# Timer_CMD_REV2.net
KiCad netlist of a schematic drawn in EAGLE
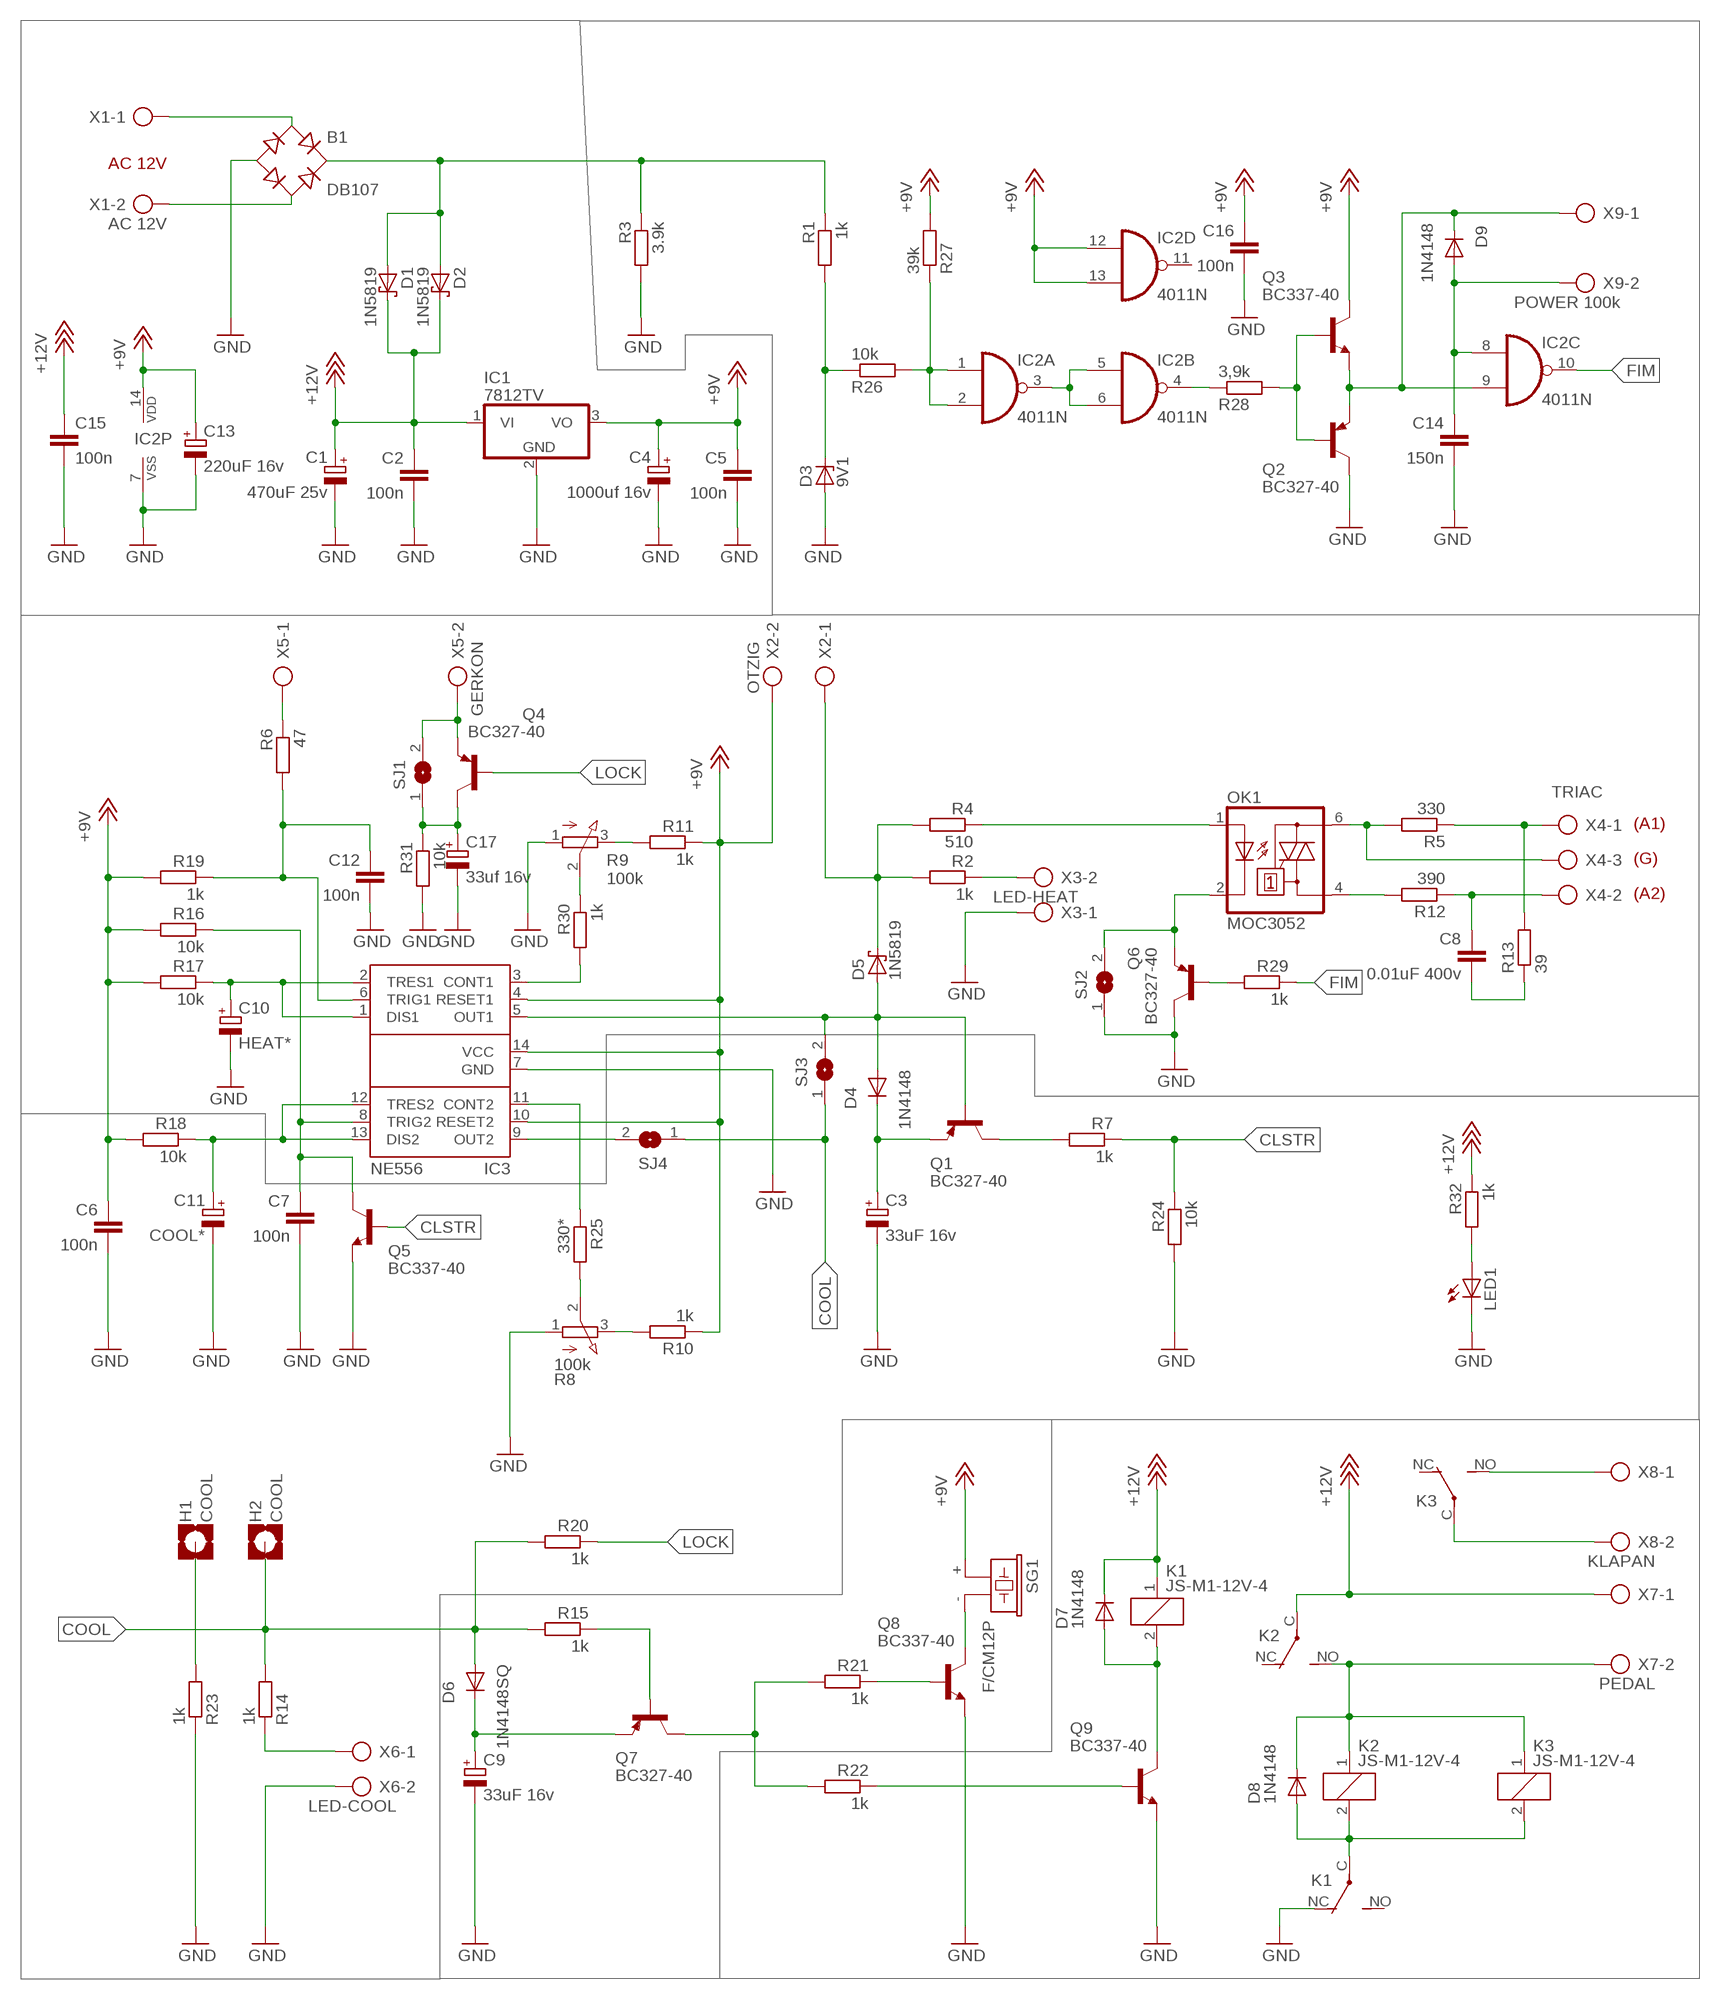
[diagram p0: schematic, sheet 1]

(export (version "E")
  (design (tool "Eeschema 10.0.6"))
  (components
    (comp (ref "B1")
      (value "DB107")
      (footprint "eagle-import:DB")
      (libsource (lib "eagle-import") (part "DB?GDB107"))
    )
    (comp (ref "C1")
      (value "470uF 25v")
      (footprint "eagle-import:E3,5-8")
      (libsource (lib "eagle-import") (part "CPOL-EUE3.5-8"))
    )
    (comp (ref "C2")
      (value "100n")
      (footprint "eagle-import:C050-035X075")
      (libsource (lib "eagle-import") (part "C-EU050-035X075"))
    )
    (comp (ref "C3")
      (value "33uF 16v")
      (footprint "eagle-import:E3,5-8")
      (libsource (lib "eagle-import") (part "CPOL-EUE3.5-8"))
    )
    (comp (ref "C4")
      (value "1000uf 16v")
      (footprint "eagle-import:E5-10,5")
      (libsource (lib "eagle-import") (part "CPOL-EUE5-10.5"))
    )
    (comp (ref "C5")
      (value "100n")
      (footprint "eagle-import:C050-035X075")
      (libsource (lib "eagle-import") (part "C-EU050-035X075"))
    )
    (comp (ref "C6")
      (value "100n")
      (footprint "eagle-import:C025-030X050")
      (libsource (lib "eagle-import") (part "C-EU025-030X050"))
    )
    (comp (ref "C7")
      (value "100n")
      (footprint "eagle-import:C025-030X050")
      (libsource (lib "eagle-import") (part "C-EU025-030X050"))
    )
    (comp (ref "C8")
      (value "0.01uF 400v")
      (footprint "eagle-import:C075-063X106")
      (libsource (lib "eagle-import") (part "C-EU075-063X106"))
    )
    (comp (ref "C9")
      (value "33uF 16v")
      (footprint "eagle-import:E3,5-8")
      (libsource (lib "eagle-import") (part "CPOL-EUE3.5-8"))
    )
    (comp (ref "C10")
      (value "HEAT*")
      (footprint "eagle-import:E3,5-10")
      (libsource (lib "eagle-import") (part "CPOL-EUE3.5-10"))
    )
    (comp (ref "C11")
      (value "COOL*")
      (footprint "eagle-import:E3,5-10")
      (libsource (lib "eagle-import") (part "CPOL-EUE3.5-10"))
    )
    (comp (ref "C12")
      (value "100n")
      (footprint "eagle-import:C025-030X050")
      (libsource (lib "eagle-import") (part "C-EU025-030X050"))
    )
    (comp (ref "C13")
      (value "220uF 16v")
      (footprint "eagle-import:E3,5-8")
      (libsource (lib "eagle-import") (part "CPOL-EUE3.5-8"))
    )
    (comp (ref "C14")
      (value "150n")
      (footprint "eagle-import:C050-035X075")
      (libsource (lib "eagle-import") (part "C-EU050-035X075"))
    )
    (comp (ref "C15")
      (value "100n")
      (footprint "eagle-import:C050-035X075")
      (libsource (lib "eagle-import") (part "C-EU050-035X075"))
    )
    (comp (ref "C16")
      (value "100n")
      (footprint "eagle-import:C050-035X075")
      (libsource (lib "eagle-import") (part "C-EU050-035X075"))
    )
    (comp (ref "C17")
      (value "33uf 16v")
      (footprint "eagle-import:E2,5-6")
      (libsource (lib "eagle-import") (part "CPOL-EUE2.5-6"))
    )
    (comp (ref "D1")
      (value "1N5819")
      (footprint "eagle-import:DO41-7.6")
      (libsource (lib "eagle-import") (part "1N5819-T"))
    )
    (comp (ref "D2")
      (value "1N5819")
      (footprint "eagle-import:DO41-7.6")
      (libsource (lib "eagle-import") (part "1N5819-T"))
    )
    (comp (ref "D3")
      (value "9V1")
      (footprint "eagle-import:DO41Z12")
      (libsource (lib "eagle-import") (part "1N4728_"))
    )
    (comp (ref "D4")
      (value "1N4148")
      (footprint "eagle-import:DO35-7SQ")
      (libsource (lib "eagle-import") (part "1N4148S"))
    )
    (comp (ref "D5")
      (value "1N5819")
      (footprint "eagle-import:DO41-7.6")
      (libsource (lib "eagle-import") (part "1N5819-T"))
    )
    (comp (ref "D6")
      (value "1N4148SQ")
      (footprint "eagle-import:DO35-10_SQ")
      (libsource (lib "eagle-import") (part "1N4148SQ"))
    )
    (comp (ref "D7")
      (value "1N4148")
      (footprint "eagle-import:DO35-7SQ")
      (libsource (lib "eagle-import") (part "1N4148S"))
    )
    (comp (ref "D8")
      (value "1N4148")
      (footprint "eagle-import:DO35-7SQ")
      (libsource (lib "eagle-import") (part "1N4148S"))
    )
    (comp (ref "D9")
      (value "1N4148")
      (footprint "eagle-import:DO35-7SQ")
      (libsource (lib "eagle-import") (part "1N4148S"))
    )
    (comp (ref "H1")
      (value "COOL")
      (footprint "eagle-import:4MM-PAD-SQUARE")
      (libsource (lib "eagle-import") (part "MOUNT-PAD-SQUARE"))
    )
    (comp (ref "H2")
      (value "COOL")
      (footprint "eagle-import:4MM-PAD-SQUARE")
      (libsource (lib "eagle-import") (part "MOUNT-PAD-SQUARE"))
    )
    (comp (ref "IC1")
      (value "7812TV")
      (footprint "eagle-import:TO220V")
      (libsource (lib "eagle-import") (part "78TV12"))
    )
    (comp (ref "IC2")
      (value "4011N")
      (footprint "eagle-import:DIL14")
      (libsource (lib "eagle-import") (part "4011N"))
    )
    (comp (ref "IC3")
      (value "NE556")
      (footprint "eagle-import:DIL14")
      (libsource (lib "eagle-import") (part "NE556"))
    )
    (comp (ref "K1")
      (value "JS-M1-12V-4")
      (footprint "eagle-import:JS-M")
      (fields (field (name "MPN") "JSM1-12V-4"))
      (libsource (lib "eagle-import") (part "JS-M1-12V-4"))
    )
    (comp (ref "K2")
      (value "JS-M1-12V-4")
      (footprint "eagle-import:JS-M")
      (fields (field (name "MPN") "JSM1-12V-4"))
      (libsource (lib "eagle-import") (part "JS-M1-12V-4"))
    )
    (comp (ref "K3")
      (value "JS-M1-12V-4")
      (footprint "eagle-import:JS-M")
      (fields (field (name "MPN") "JSM1-12V-4"))
      (libsource (lib "eagle-import") (part "JS-M1-12V-4"))
    )
    (comp (ref "LED1")
      (value "LED3MM")
      (footprint "eagle-import:LED3MM")
      (libsource (lib "eagle-import") (part "LED3MM"))
    )
    (comp (ref "OK1")
      (value "MOC3052")
      (footprint "eagle-import:DIL06")
      (fields (field (name "MF") "FAIRCHILD SEMICONDUCTOR") (field (name "MPN") "MOC3042-M"))
      (libsource (lib "eagle-import") (part "MOC3042M"))
    )
    (comp (ref "Q1")
      (value "BC327-40")
      (footprint "eagle-import:TO92-EBC")
      (libsource (lib "eagle-import") (part "BC327-40"))
    )
    (comp (ref "Q2")
      (value "BC327-40")
      (footprint "eagle-import:TO92-EBC")
      (libsource (lib "eagle-import") (part "BC327-40"))
    )
    (comp (ref "Q3")
      (value "BC337-40")
      (footprint "eagle-import:TO92-EBC")
      (libsource (lib "eagle-import") (part "BC338-40"))
    )
    (comp (ref "Q4")
      (value "BC327-40")
      (footprint "eagle-import:TO92-EBC")
      (libsource (lib "eagle-import") (part "BC327-40"))
    )
    (comp (ref "Q5")
      (value "BC337-40")
      (footprint "eagle-import:TO92-EBC")
      (libsource (lib "eagle-import") (part "BC338-40"))
    )
    (comp (ref "Q6")
      (value "BC327-40")
      (footprint "eagle-import:TO92-EBC")
      (libsource (lib "eagle-import") (part "BC327-40"))
    )
    (comp (ref "Q7")
      (value "BC327-40")
      (footprint "eagle-import:TO92-EBC")
      (libsource (lib "eagle-import") (part "BC327-40"))
    )
    (comp (ref "Q8")
      (value "BC337-40")
      (footprint "eagle-import:TO92-EBC")
      (libsource (lib "eagle-import") (part "BC338-40"))
    )
    (comp (ref "Q9")
      (value "BC337-40")
      (footprint "eagle-import:TO92-EBC")
      (libsource (lib "eagle-import") (part "BC338-40"))
    )
    (comp (ref "R1")
      (value "1k")
      (footprint "eagle-import:0207_10")
      (libsource (lib "eagle-import") (part "R-EU_0207/10"))
    )
    (comp (ref "R2")
      (value "1k")
      (footprint "eagle-import:0207_10")
      (libsource (lib "eagle-import") (part "R-EU_0207/10"))
    )
    (comp (ref "R3")
      (value "3.9k")
      (footprint "eagle-import:0207_10")
      (libsource (lib "eagle-import") (part "R-EU_0207/10"))
    )
    (comp (ref "R4")
      (value "510")
      (footprint "eagle-import:0207_10")
      (libsource (lib "eagle-import") (part "R-EU_0207/10"))
    )
    (comp (ref "R5")
      (value "330")
      (footprint "eagle-import:0207_10")
      (libsource (lib "eagle-import") (part "R-EU_0207/10"))
    )
    (comp (ref "R6")
      (value "47")
      (footprint "eagle-import:0207_10")
      (libsource (lib "eagle-import") (part "R-EU_0207/10"))
    )
    (comp (ref "R7")
      (value "1k")
      (footprint "eagle-import:0207_10")
      (libsource (lib "eagle-import") (part "R-EU_0207/10"))
    )
    (comp (ref "R8")
      (value "100k")
      (footprint "eagle-import:3RP_1610N")
      (libsource (lib "eagle-import") (part "3RP/1610N"))
    )
    (comp (ref "R9")
      (value "100k")
      (footprint "eagle-import:3RP_1610N")
      (libsource (lib "eagle-import") (part "3RP/1610N"))
    )
    (comp (ref "R10")
      (value "1k")
      (footprint "eagle-import:0207_10")
      (libsource (lib "eagle-import") (part "R-EU_0207/10"))
    )
    (comp (ref "R11")
      (value "1k")
      (footprint "eagle-import:0207_10")
      (libsource (lib "eagle-import") (part "R-EU_0207/10"))
    )
    (comp (ref "R12")
      (value "390")
      (footprint "eagle-import:0207_10")
      (libsource (lib "eagle-import") (part "R-EU_0207/10"))
    )
    (comp (ref "R13")
      (value "39")
      (footprint "eagle-import:0411_12")
      (libsource (lib "eagle-import") (part "R-EU_0411/12"))
    )
    (comp (ref "R14")
      (value "1k")
      (footprint "eagle-import:0207_10")
      (libsource (lib "eagle-import") (part "R-EU_0207/10"))
    )
    (comp (ref "R15")
      (value "1k")
      (footprint "eagle-import:0207_10")
      (libsource (lib "eagle-import") (part "R-EU_0207/10"))
    )
    (comp (ref "R16")
      (value "10k")
      (footprint "eagle-import:0207_10")
      (libsource (lib "eagle-import") (part "R-EU_0207/10"))
    )
    (comp (ref "R17")
      (value "10k")
      (footprint "eagle-import:0207_10")
      (libsource (lib "eagle-import") (part "R-EU_0207/10"))
    )
    (comp (ref "R18")
      (value "10k")
      (footprint "eagle-import:0207_10")
      (libsource (lib "eagle-import") (part "R-EU_0207/10"))
    )
    (comp (ref "R19")
      (value "1k")
      (footprint "eagle-import:0207_10")
      (libsource (lib "eagle-import") (part "R-EU_0207/10"))
    )
    (comp (ref "R20")
      (value "1k")
      (footprint "eagle-import:0207_10")
      (libsource (lib "eagle-import") (part "R-EU_0207/10"))
    )
    (comp (ref "R21")
      (value "1k")
      (footprint "eagle-import:0207_10")
      (libsource (lib "eagle-import") (part "R-EU_0207/10"))
    )
    (comp (ref "R22")
      (value "1k")
      (footprint "eagle-import:0207_10")
      (libsource (lib "eagle-import") (part "R-EU_0207/10"))
    )
    (comp (ref "R23")
      (value "1k")
      (footprint "eagle-import:0207_10")
      (libsource (lib "eagle-import") (part "R-EU_0207/10"))
    )
    (comp (ref "R24")
      (value "10k")
      (footprint "eagle-import:0207_10")
      (libsource (lib "eagle-import") (part "R-EU_0207/10"))
    )
    (comp (ref "R25")
      (value "330*")
      (footprint "eagle-import:0207_10")
      (libsource (lib "eagle-import") (part "R-EU_0207/10"))
    )
    (comp (ref "R26")
      (value "10k")
      (footprint "eagle-import:0207_10")
      (libsource (lib "eagle-import") (part "R-EU_0207/10"))
    )
    (comp (ref "R27")
      (value "39k")
      (footprint "eagle-import:0207_10")
      (libsource (lib "eagle-import") (part "R-EU_0207/10"))
    )
    (comp (ref "R28")
      (value "3,9k")
      (footprint "eagle-import:0207_10")
      (libsource (lib "eagle-import") (part "R-EU_0207/10"))
    )
    (comp (ref "R29")
      (value "1k")
      (footprint "eagle-import:0207_10")
      (libsource (lib "eagle-import") (part "R-EU_0207/10"))
    )
    (comp (ref "R30")
      (value "1k")
      (footprint "eagle-import:0207_11")
      (libsource (lib "eagle-import") (part "R-EU_0207/11"))
    )
    (comp (ref "R31")
      (value "10k")
      (footprint "eagle-import:0207_10")
      (libsource (lib "eagle-import") (part "R-EU_0207/10"))
    )
    (comp (ref "R32")
      (value "1k")
      (footprint "eagle-import:0207_10")
      (libsource (lib "eagle-import") (part "R-EU_0207/10"))
    )
    (comp (ref "SG1")
      (value "F/CM12P")
      (footprint "eagle-import:F_CM12P")
      (libsource (lib "eagle-import") (part "F/CM12P"))
    )
    (comp (ref "SJ1") (value "SJ") (footprint "eagle-import:SJ") (libsource (lib "eagle-import") (part "SJ")))
    (comp (ref "SJ2") (value "SJ") (footprint "eagle-import:SJ") (libsource (lib "eagle-import") (part "SJ")))
    (comp (ref "SJ3") (value "SJ") (footprint "eagle-import:SJ") (libsource (lib "eagle-import") (part "SJ")))
    (comp (ref "SJ4") (value "SJ") (footprint "eagle-import:SJ") (libsource (lib "eagle-import") (part "SJ")))
    (comp (ref "X1")
      (value "AC 12V")
      (footprint "eagle-import:AK500_2")
      (libsource (lib "eagle-import") (part "AK500/2"))
    )
    (comp (ref "X2")
      (value "OTZIG")
      (footprint "eagle-import:AK500_2")
      (libsource (lib "eagle-import") (part "AK500/2"))
    )
    (comp (ref "X3")
      (value "LED-HEAT")
      (footprint "eagle-import:AK500_2")
      (libsource (lib "eagle-import") (part "AK500/2"))
    )
    (comp (ref "X4")
      (value "TRIAC")
      (footprint "eagle-import:AK500_3")
      (libsource (lib "eagle-import") (part "AK500/3"))
    )
    (comp (ref "X5")
      (value "GERKON")
      (footprint "eagle-import:AK500_2")
      (libsource (lib "eagle-import") (part "AK500/2"))
    )
    (comp (ref "X6")
      (value "LED-COOL")
      (footprint "eagle-import:AK500_2")
      (libsource (lib "eagle-import") (part "AK500/2"))
    )
    (comp (ref "X7")
      (value "PEDAL")
      (footprint "eagle-import:AK500_2")
      (libsource (lib "eagle-import") (part "AK500/2"))
    )
    (comp (ref "X8")
      (value "KLAPAN")
      (footprint "eagle-import:AK500_2")
      (libsource (lib "eagle-import") (part "AK500/2"))
    )
    (comp (ref "X9")
      (value "POWER 100k")
      (footprint "eagle-import:AK500_2")
      (libsource (lib "eagle-import") (part "AK500/2"))
    )
  )
  (nets
    (net (code "1") (name "+9V") (class "Default")
      (node (ref "C13") (pin "+") (pinfunction "+_+") (pintype "passive"))
      (node (ref "C16") (pin "1") (pinfunction "1_1") (pintype "passive"))
      (node (ref "C4") (pin "+") (pinfunction "+_+") (pintype "passive"))
      (node (ref "C5") (pin "1") (pinfunction "1_1") (pintype "passive"))
      (node (ref "C6") (pin "1") (pinfunction "1_1") (pintype "passive"))
      (node (ref "IC1") (pin "3") (pinfunction "VO_3") (pintype "passive"))
      (node (ref "IC2") (pin "12") (pinfunction "I0_12") (pintype "input"))
      (node (ref "IC2") (pin "13") (pinfunction "I1_13") (pintype "input"))
      (node (ref "IC2") (pin "14") (pinfunction "VDD_14") (pintype "power_in"))
      (node (ref "IC3") (pin "10") (pinfunction "RESET2_10") (pintype "input"))
      (node (ref "IC3") (pin "14") (pinfunction "VCC_14") (pintype "power_in"))
      (node (ref "IC3") (pin "4") (pinfunction "RESET1_4") (pintype "input"))
      (node (ref "Q3") (pin "C") (pinfunction "C_C") (pintype "passive"))
      (node (ref "R10") (pin "1") (pinfunction "1_1") (pintype "passive"))
      (node (ref "R11") (pin "1") (pinfunction "1_1") (pintype "passive"))
      (node (ref "R16") (pin "2") (pinfunction "2_2") (pintype "passive"))
      (node (ref "R17") (pin "2") (pinfunction "2_2") (pintype "passive"))
      (node (ref "R18") (pin "2") (pinfunction "2_2") (pintype "passive"))
      (node (ref "R19") (pin "2") (pinfunction "2_2") (pintype "passive"))
      (node (ref "R27") (pin "2") (pinfunction "2_2") (pintype "passive"))
      (node (ref "SG1") (pin "+") (pinfunction "1_+") (pintype "passive"))
      (node (ref "X2") (pin "2") (pinfunction "KL_2") (pintype "passive"))
    )
    (net (code "2") (name "+12V") (class "Default")
      (node (ref "C1") (pin "+") (pinfunction "+_+") (pintype "passive"))
      (node (ref "C15") (pin "1") (pinfunction "1_1") (pintype "passive"))
      (node (ref "C2") (pin "1") (pinfunction "1_1") (pintype "passive"))
      (node (ref "D1") (pin "C") (pinfunction "C_C") (pintype "passive"))
      (node (ref "D2") (pin "C") (pinfunction "C_C") (pintype "passive"))
      (node (ref "D7") (pin "C") (pinfunction "C_C") (pintype "passive"))
      (node (ref "IC1") (pin "1") (pinfunction "VI_1") (pintype "input"))
      (node (ref "K1") (pin "1") (pinfunction "1_1") (pintype "passive"))
      (node (ref "K2") (pin "C") (pinfunction "P_C") (pintype "passive"))
      (node (ref "R32") (pin "1") (pinfunction "1_1") (pintype "passive"))
      (node (ref "X7") (pin "1") (pinfunction "KL_1") (pintype "passive"))
    )
    (net (code "3") (name "CLSTR") (class "Default")
      (node (ref "Q5") (pin "B") (pinfunction "B_B") (pintype "passive"))
      (node (ref "R24") (pin "1") (pinfunction "1_1") (pintype "passive"))
      (node (ref "R7") (pin "1") (pinfunction "1_1") (pintype "passive"))
    )
    (net (code "4") (name "COOL") (class "Default")
      (node (ref "D6") (pin "A") (pinfunction "A_A") (pintype "passive"))
      (node (ref "H2") (pin "B2,8") (pinfunction "MOUNT_B2,8") (pintype "passive"))
      (node (ref "R14") (pin "2") (pinfunction "2_2") (pintype "passive"))
      (node (ref "R15") (pin "2") (pinfunction "2_2") (pintype "passive"))
      (node (ref "R20") (pin "2") (pinfunction "2_2") (pintype "passive"))
      (node (ref "SJ3") (pin "1") (pinfunction "1_1") (pintype "passive"))
      (node (ref "SJ4") (pin "1") (pinfunction "1_1") (pintype "passive"))
    )
    (net (code "5") (name "FIM") (class "Default")
      (node (ref "IC2") (pin "10") (pinfunction "O_10") (pintype "output"))
      (node (ref "R29") (pin "1") (pinfunction "1_1") (pintype "passive"))
    )
    (net (code "6") (name "GND") (class "Default")
      (node (ref "B1") (pin "-") (pinfunction "-_-") (pintype "passive"))
      (node (ref "C1") (pin "-") (pinfunction "-_-") (pintype "passive"))
      (node (ref "C10") (pin "-") (pinfunction "-_-") (pintype "passive"))
      (node (ref "C11") (pin "-") (pinfunction "-_-") (pintype "passive"))
      (node (ref "C12") (pin "2") (pinfunction "2_2") (pintype "passive"))
      (node (ref "C13") (pin "-") (pinfunction "-_-") (pintype "passive"))
      (node (ref "C14") (pin "2") (pinfunction "2_2") (pintype "passive"))
      (node (ref "C15") (pin "2") (pinfunction "2_2") (pintype "passive"))
      (node (ref "C16") (pin "2") (pinfunction "2_2") (pintype "passive"))
      (node (ref "C17") (pin "-") (pinfunction "-_-") (pintype "passive"))
      (node (ref "C2") (pin "2") (pinfunction "2_2") (pintype "passive"))
      (node (ref "C3") (pin "-") (pinfunction "-_-") (pintype "passive"))
      (node (ref "C4") (pin "-") (pinfunction "-_-") (pintype "passive"))
      (node (ref "C5") (pin "2") (pinfunction "2_2") (pintype "passive"))
      (node (ref "C6") (pin "2") (pinfunction "2_2") (pintype "passive"))
      (node (ref "C7") (pin "2") (pinfunction "2_2") (pintype "passive"))
      (node (ref "C9") (pin "-") (pinfunction "-_-") (pintype "passive"))
      (node (ref "D3") (pin "A") (pinfunction "A_A") (pintype "passive"))
      (node (ref "IC1") (pin "2") (pinfunction "GND_2") (pintype "passive"))
      (node (ref "IC2") (pin "7") (pinfunction "VSS_7") (pintype "power_in"))
      (node (ref "IC3") (pin "7") (pinfunction "GND_7") (pintype "power_in"))
      (node (ref "K1") (pin "NC") (pinfunction "O_NC") (pintype "passive"))
      (node (ref "LED1") (pin "K") (pinfunction "C_K") (pintype "passive"))
      (node (ref "Q2") (pin "C") (pinfunction "C_C") (pintype "passive"))
      (node (ref "Q5") (pin "E") (pinfunction "E_E") (pintype "passive"))
      (node (ref "Q6") (pin "C") (pinfunction "C_C") (pintype "passive"))
      (node (ref "Q8") (pin "E") (pinfunction "E_E") (pintype "passive"))
      (node (ref "Q9") (pin "E") (pinfunction "E_E") (pintype "passive"))
      (node (ref "R23") (pin "1") (pinfunction "1_1") (pintype "passive"))
      (node (ref "R24") (pin "2") (pinfunction "2_2") (pintype "passive"))
      (node (ref "R3") (pin "2") (pinfunction "2_2") (pintype "passive"))
      (node (ref "R31") (pin "2") (pinfunction "2_2") (pintype "passive"))
      (node (ref "R8") (pin "1") (pinfunction "A_1") (pintype "passive"))
      (node (ref "R9") (pin "1") (pinfunction "A_1") (pintype "passive"))
      (node (ref "SJ2") (pin "1") (pinfunction "1_1") (pintype "passive"))
      (node (ref "X3") (pin "1") (pinfunction "KL_1") (pintype "passive"))
      (node (ref "X6") (pin "2") (pinfunction "KL_2") (pintype "passive"))
    )
    (net (code "7") (name "LOCK") (class "Default")
      (node (ref "Q4") (pin "B") (pinfunction "B_B") (pintype "passive"))
      (node (ref "R20") (pin "1") (pinfunction "1_1") (pintype "passive"))
    )
    (net (code "8") (name "Net-(B1-Pad+)") (class "Default")
      (node (ref "B1") (pin "+") (pinfunction "+_+") (pintype "passive"))
      (node (ref "D1") (pin "A") (pinfunction "A_A") (pintype "passive"))
      (node (ref "D2") (pin "A") (pinfunction "A_A") (pintype "passive"))
      (node (ref "R1") (pin "1") (pinfunction "1_1") (pintype "passive"))
      (node (ref "R3") (pin "1") (pinfunction "1_1") (pintype "passive"))
    )
    (net (code "9") (name "Net-(C3-Pad+)") (class "Default")
      (node (ref "C3") (pin "+") (pinfunction "+_+") (pintype "passive"))
      (node (ref "D4") (pin "C") (pinfunction "C_C") (pintype "passive"))
      (node (ref "Q1") (pin "E") (pinfunction "E_E") (pintype "passive"))
    )
    (net (code "10") (name "Net-(C8-Pad2)") (class "Default")
      (node (ref "C8") (pin "2") (pinfunction "2_2") (pintype "passive"))
      (node (ref "R13") (pin "1") (pinfunction "1_1") (pintype "passive"))
    )
    (net (code "11") (name "Net-(C9-Pad+)") (class "Default")
      (node (ref "C9") (pin "+") (pinfunction "+_+") (pintype "passive"))
      (node (ref "D6") (pin "C") (pinfunction "C_C") (pintype "passive"))
      (node (ref "Q7") (pin "E") (pinfunction "E_E") (pintype "passive"))
    )
    (net (code "12") (name "Net-(C17-Pad+)") (class "Default")
      (node (ref "C17") (pin "+") (pinfunction "+_+") (pintype "passive"))
      (node (ref "Q4") (pin "C") (pinfunction "C_C") (pintype "passive"))
      (node (ref "R31") (pin "1") (pinfunction "1_1") (pintype "passive"))
      (node (ref "SJ1") (pin "1") (pinfunction "1_1") (pintype "passive"))
    )
    (net (code "13") (name "Net-(D3-PadC)") (class "Default")
      (node (ref "D3") (pin "C") (pinfunction "C_C") (pintype "passive"))
      (node (ref "R1") (pin "2") (pinfunction "2_2") (pintype "passive"))
      (node (ref "R26") (pin "1") (pinfunction "1_1") (pintype "passive"))
    )
    (net (code "14") (name "Net-(D7-PadA)") (class "Default")
      (node (ref "D7") (pin "A") (pinfunction "A_A") (pintype "passive"))
      (node (ref "K1") (pin "2") (pinfunction "2_2") (pintype "passive"))
      (node (ref "Q9") (pin "C") (pinfunction "C_C") (pintype "passive"))
    )
    (net (code "15") (name "Net-(H1-MOUNT)") (class "Default")
      (node (ref "H1") (pin "B2,8") (pinfunction "MOUNT_B2,8") (pintype "passive"))
      (node (ref "R23") (pin "2") (pinfunction "2_2") (pintype "passive"))
    )
    (net (code "16") (name "Net-(IC2A-I0)") (class "Default")
      (node (ref "IC2") (pin "1") (pinfunction "I0_1") (pintype "input"))
      (node (ref "IC2") (pin "2") (pinfunction "I1_2") (pintype "input"))
      (node (ref "R26") (pin "2") (pinfunction "2_2") (pintype "passive"))
      (node (ref "R27") (pin "1") (pinfunction "1_1") (pintype "passive"))
    )
    (net (code "17") (name "Net-(IC2A-O)") (class "Default")
      (node (ref "IC2") (pin "3") (pinfunction "O_3") (pintype "output"))
      (node (ref "IC2") (pin "5") (pinfunction "I0_5") (pintype "input"))
      (node (ref "IC2") (pin "6") (pinfunction "I1_6") (pintype "input"))
    )
    (net (code "18") (name "Net-(IC2B-O)") (class "Default")
      (node (ref "IC2") (pin "4") (pinfunction "O_4") (pintype "output"))
      (node (ref "R28") (pin "1") (pinfunction "1_1") (pintype "passive"))
    )
    (net (code "19") (name "Net-(IC2C-I0)") (class "Default")
      (node (ref "C14") (pin "1") (pinfunction "1_1") (pintype "passive"))
      (node (ref "D9") (pin "A") (pinfunction "A_A") (pintype "passive"))
      (node (ref "IC2") (pin "8") (pinfunction "I0_8") (pintype "input"))
      (node (ref "X9") (pin "2") (pinfunction "KL_2") (pintype "passive"))
    )
    (net (code "20") (name "Net-(IC2C-I1)") (class "Default")
      (node (ref "D9") (pin "C") (pinfunction "C_C") (pintype "passive"))
      (node (ref "IC2") (pin "9") (pinfunction "I1_9") (pintype "input"))
      (node (ref "Q2") (pin "E") (pinfunction "E_E") (pintype "passive"))
      (node (ref "Q3") (pin "E") (pinfunction "E_E") (pintype "passive"))
      (node (ref "X9") (pin "1") (pinfunction "KL_1") (pintype "passive"))
    )
    (net (code "21") (name "Net-(IC3-CONT1)") (class "Default")
      (node (ref "IC3") (pin "3") (pinfunction "CONT1_3") (pintype "input"))
      (node (ref "R30") (pin "2") (pinfunction "2_2") (pintype "passive"))
    )
    (net (code "22") (name "Net-(IC3-CONT2)") (class "Default")
      (node (ref "IC3") (pin "11") (pinfunction "CONT2_11") (pintype "input"))
      (node (ref "R25") (pin "1") (pinfunction "1_1") (pintype "passive"))
    )
    (net (code "23") (name "Net-(IC3-DIS1)") (class "Default")
      (node (ref "C10") (pin "+") (pinfunction "+_+") (pintype "passive"))
      (node (ref "IC3") (pin "1") (pinfunction "DIS1_1") (pintype "input"))
      (node (ref "IC3") (pin "2") (pinfunction "TRES1_2") (pintype "input"))
      (node (ref "R17") (pin "1") (pinfunction "1_1") (pintype "passive"))
    )
    (net (code "24") (name "Net-(IC3-DIS2)") (class "Default")
      (node (ref "C11") (pin "+") (pinfunction "+_+") (pintype "passive"))
      (node (ref "IC3") (pin "12") (pinfunction "TRES2_12") (pintype "input"))
      (node (ref "IC3") (pin "13") (pinfunction "DIS2_13") (pintype "input"))
      (node (ref "R18") (pin "1") (pinfunction "1_1") (pintype "passive"))
    )
    (net (code "25") (name "Net-(IC3-OUT1)") (class "Default")
      (node (ref "D4") (pin "A") (pinfunction "A_A") (pintype "passive"))
      (node (ref "D5") (pin "A") (pinfunction "A_A") (pintype "passive"))
      (node (ref "IC3") (pin "5") (pinfunction "OUT1_5") (pintype "output"))
      (node (ref "Q1") (pin "B") (pinfunction "B_B") (pintype "passive"))
      (node (ref "SJ3") (pin "2") (pinfunction "2_2") (pintype "passive"))
    )
    (net (code "26") (name "Net-(IC3-OUT2)") (class "Default")
      (node (ref "IC3") (pin "9") (pinfunction "OUT2_9") (pintype "output"))
      (node (ref "SJ4") (pin "2") (pinfunction "2_2") (pintype "passive"))
    )
    (net (code "27") (name "Net-(IC3-TRIG1)") (class "Default")
      (node (ref "C12") (pin "1") (pinfunction "1_1") (pintype "passive"))
      (node (ref "IC3") (pin "6") (pinfunction "TRIG1_6") (pintype "input"))
      (node (ref "R19") (pin "1") (pinfunction "1_1") (pintype "passive"))
      (node (ref "R6") (pin "2") (pinfunction "2_2") (pintype "passive"))
    )
    (net (code "28") (name "Net-(IC3-TRIG2)") (class "Default")
      (node (ref "C7") (pin "1") (pinfunction "1_1") (pintype "passive"))
      (node (ref "IC3") (pin "8") (pinfunction "TRIG2_8") (pintype "input"))
      (node (ref "Q5") (pin "C") (pinfunction "C_C") (pintype "passive"))
      (node (ref "R16") (pin "1") (pinfunction "1_1") (pintype "passive"))
    )
    (net (code "29") (name "Net-(K1B-P)") (class "Default")
      (node (ref "D8") (pin "A") (pinfunction "A_A") (pintype "passive"))
      (node (ref "K1") (pin "C") (pinfunction "P_C") (pintype "passive"))
      (node (ref "K2") (pin "2") (pinfunction "2_2") (pintype "passive"))
      (node (ref "K3") (pin "2") (pinfunction "2_2") (pintype "passive"))
    )
    (net (code "30") (name "Net-(K2B-S)") (class "Default")
      (node (ref "D8") (pin "C") (pinfunction "C_C") (pintype "passive"))
      (node (ref "K2") (pin "1") (pinfunction "1_1") (pintype "passive"))
      (node (ref "K2") (pin "NO") (pinfunction "S_NO") (pintype "passive"))
      (node (ref "K3") (pin "1") (pinfunction "1_1") (pintype "passive"))
      (node (ref "X7") (pin "2") (pinfunction "KL_2") (pintype "passive"))
    )
    (net (code "31") (name "Net-(K3B-P)") (class "Default")
      (node (ref "K3") (pin "C") (pinfunction "P_C") (pintype "passive"))
      (node (ref "X8") (pin "2") (pinfunction "KL_2") (pintype "passive"))
    )
    (net (code "32") (name "Net-(K3B-S)") (class "Default")
      (node (ref "K3") (pin "NO") (pinfunction "S_NO") (pintype "passive"))
      (node (ref "X8") (pin "1") (pinfunction "KL_1") (pintype "passive"))
    )
    (net (code "33") (name "Net-(LED1-PadA)") (class "Default")
      (node (ref "LED1") (pin "A") (pinfunction "A_A") (pintype "passive"))
      (node (ref "R32") (pin "2") (pinfunction "2_2") (pintype "passive"))
    )
    (net (code "34") (name "Net-(OK1-A)") (class "Default")
      (node (ref "OK1") (pin "1") (pinfunction "A_1") (pintype "passive"))
      (node (ref "R4") (pin "1") (pinfunction "1_1") (pintype "passive"))
    )
    (net (code "35") (name "Net-(OK1-A1)") (class "Default")
      (node (ref "OK1") (pin "4") (pinfunction "A1_4") (pintype "passive"))
      (node (ref "R12") (pin "2") (pinfunction "2_2") (pintype "passive"))
    )
    (net (code "36") (name "Net-(OK1-A2)") (class "Default")
      (node (ref "OK1") (pin "6") (pinfunction "A2_6") (pintype "passive"))
      (node (ref "R5") (pin "2") (pinfunction "2_2") (pintype "passive"))
      (node (ref "X4") (pin "3") (pinfunction "KL_3") (pintype "passive"))
    )
    (net (code "37") (name "Net-(OK1-C)") (class "Default")
      (node (ref "OK1") (pin "2") (pinfunction "C_2") (pintype "passive"))
      (node (ref "Q6") (pin "E") (pinfunction "E_E") (pintype "passive"))
      (node (ref "SJ2") (pin "2") (pinfunction "2_2") (pintype "passive"))
    )
    (net (code "38") (name "Net-(Q1-PadC)") (class "Default")
      (node (ref "Q1") (pin "C") (pinfunction "C_C") (pintype "passive"))
      (node (ref "R7") (pin "2") (pinfunction "2_2") (pintype "passive"))
    )
    (net (code "39") (name "Net-(Q2-PadB)") (class "Default")
      (node (ref "Q2") (pin "B") (pinfunction "B_B") (pintype "passive"))
      (node (ref "Q3") (pin "B") (pinfunction "B_B") (pintype "passive"))
      (node (ref "R28") (pin "2") (pinfunction "2_2") (pintype "passive"))
    )
    (net (code "40") (name "Net-(Q6-PadB)") (class "Default")
      (node (ref "Q6") (pin "B") (pinfunction "B_B") (pintype "passive"))
      (node (ref "R29") (pin "2") (pinfunction "2_2") (pintype "passive"))
    )
    (net (code "41") (name "Net-(Q7-PadB)") (class "Default")
      (node (ref "Q7") (pin "B") (pinfunction "B_B") (pintype "passive"))
      (node (ref "R15") (pin "1") (pinfunction "1_1") (pintype "passive"))
    )
    (net (code "42") (name "Net-(Q7-PadC)") (class "Default")
      (node (ref "Q7") (pin "C") (pinfunction "C_C") (pintype "passive"))
      (node (ref "R21") (pin "2") (pinfunction "2_2") (pintype "passive"))
      (node (ref "R22") (pin "2") (pinfunction "2_2") (pintype "passive"))
    )
    (net (code "43") (name "Net-(Q8-PadB)") (class "Default")
      (node (ref "Q8") (pin "B") (pinfunction "B_B") (pintype "passive"))
      (node (ref "R21") (pin "1") (pinfunction "1_1") (pintype "passive"))
    )
    (net (code "44") (name "Net-(Q9-PadB)") (class "Default")
      (node (ref "Q9") (pin "B") (pinfunction "B_B") (pintype "passive"))
      (node (ref "R22") (pin "1") (pinfunction "1_1") (pintype "passive"))
    )
    (net (code "45") (name "Net-(R8-E)") (class "Default")
      (node (ref "R10") (pin "2") (pinfunction "2_2") (pintype "passive"))
      (node (ref "R8") (pin "3") (pinfunction "E_3") (pintype "passive"))
    )
    (net (code "46") (name "Net-(R8-S)") (class "Default")
      (node (ref "R25") (pin "2") (pinfunction "2_2") (pintype "passive"))
      (node (ref "R8") (pin "2") (pinfunction "S_2") (pintype "passive"))
    )
    (net (code "47") (name "Net-(R9-E)") (class "Default")
      (node (ref "R11") (pin "2") (pinfunction "2_2") (pintype "passive"))
      (node (ref "R9") (pin "3") (pinfunction "E_3") (pintype "passive"))
    )
    (net (code "48") (name "Net-(R9-S)") (class "Default")
      (node (ref "R30") (pin "1") (pinfunction "1_1") (pintype "passive"))
      (node (ref "R9") (pin "2") (pinfunction "S_2") (pintype "passive"))
    )
    (net (code "49") (name "Net-(SG1-2)") (class "Default")
      (node (ref "Q8") (pin "C") (pinfunction "C_C") (pintype "passive"))
      (node (ref "SG1") (pin "-") (pinfunction "2_-") (pintype "passive"))
    )
    (net (code "50") (name "Net-(X1A-KL)") (class "Default")
      (node (ref "B1") (pin "AC1") (pinfunction "AC1_AC1") (pintype "passive"))
      (node (ref "X1") (pin "1") (pinfunction "KL_1") (pintype "passive"))
    )
    (net (code "51") (name "Net-(X1B-KL)") (class "Default")
      (node (ref "B1") (pin "AC2") (pinfunction "AC2_AC2") (pintype "passive"))
      (node (ref "X1") (pin "2") (pinfunction "KL_2") (pintype "passive"))
    )
    (net (code "52") (name "Net-(X2A-KL)") (class "Default")
      (node (ref "D5") (pin "C") (pinfunction "C_C") (pintype "passive"))
      (node (ref "R2") (pin "2") (pinfunction "2_2") (pintype "passive"))
      (node (ref "R4") (pin "2") (pinfunction "2_2") (pintype "passive"))
      (node (ref "X2") (pin "1") (pinfunction "KL_1") (pintype "passive"))
    )
    (net (code "53") (name "Net-(X3B-KL)") (class "Default")
      (node (ref "R2") (pin "1") (pinfunction "1_1") (pintype "passive"))
      (node (ref "X3") (pin "2") (pinfunction "KL_2") (pintype "passive"))
    )
    (net (code "54") (name "Net-(X4A-KL)") (class "Default")
      (node (ref "R13") (pin "2") (pinfunction "2_2") (pintype "passive"))
      (node (ref "R5") (pin "1") (pinfunction "1_1") (pintype "passive"))
      (node (ref "X4") (pin "1") (pinfunction "KL_1") (pintype "passive"))
    )
    (net (code "55") (name "Net-(X4B-KL)") (class "Default")
      (node (ref "C8") (pin "1") (pinfunction "1_1") (pintype "passive"))
      (node (ref "R12") (pin "1") (pinfunction "1_1") (pintype "passive"))
      (node (ref "X4") (pin "2") (pinfunction "KL_2") (pintype "passive"))
    )
    (net (code "56") (name "Net-(X5A-KL)") (class "Default")
      (node (ref "R6") (pin "1") (pinfunction "1_1") (pintype "passive"))
      (node (ref "X5") (pin "1") (pinfunction "KL_1") (pintype "passive"))
    )
    (net (code "57") (name "Net-(X5B-KL)") (class "Default")
      (node (ref "Q4") (pin "E") (pinfunction "E_E") (pintype "passive"))
      (node (ref "SJ1") (pin "2") (pinfunction "2_2") (pintype "passive"))
      (node (ref "X5") (pin "2") (pinfunction "KL_2") (pintype "passive"))
    )
    (net (code "58") (name "Net-(X6A-KL)") (class "Default")
      (node (ref "R14") (pin "1") (pinfunction "1_1") (pintype "passive"))
      (node (ref "X6") (pin "1") (pinfunction "KL_1") (pintype "passive"))
    )
    (net (code "59") (name "unconnected-(IC2D-O-Pad11)") (class "Default")
      (node (ref "IC2") (pin "11") (pinfunction "O_11") (pintype "output"))
    )
    (net (code "60") (name "unconnected-(K1B-S-PadNO)") (class "Default")
      (node (ref "K1") (pin "NO") (pinfunction "S_NO") (pintype "passive"))
    )
    (net (code "61") (name "unconnected-(K2B-O-PadNC)") (class "Default")
      (node (ref "K2") (pin "NC") (pinfunction "O_NC") (pintype "passive"))
    )
    (net (code "62") (name "unconnected-(K3B-O-PadNC)") (class "Default")
      (node (ref "K3") (pin "NC") (pinfunction "O_NC") (pintype "passive"))
    )
  )
)
